# WMCB-V2.net
KiCad netlist of a schematic drawn in Altium Designer
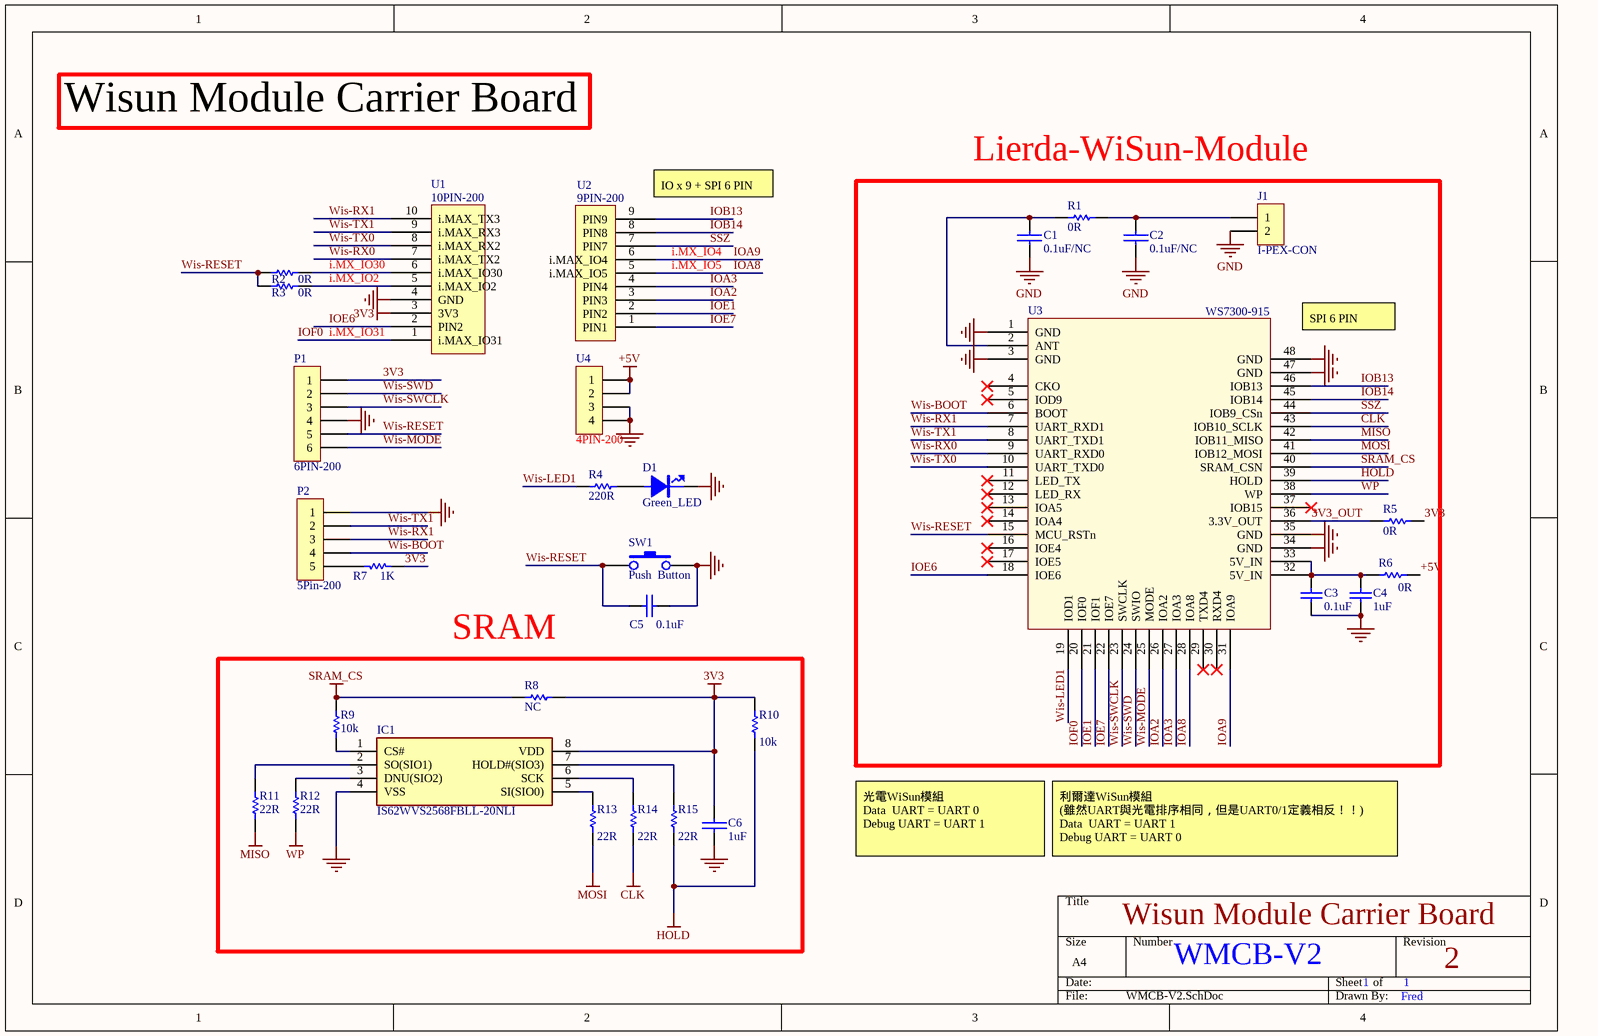
[diagram p0: WMCB-V2.SchDoc]

(export (version "E")
  (design (tool "Eeschema 10.0.6"))
  (components
    (comp (ref "C1")
      (value "0.1uF/NC")
      (footprint "0402C")
      (description "Capacitor")
      (libsource (lib "*") (part "CAP"))
    )
    (comp (ref "C2")
      (value "0.1uF/NC")
      (footprint "0402C")
      (description "Capacitor")
      (libsource (lib "*") (part "CAP"))
    )
    (comp (ref "C3")
      (value "0.1uF")
      (footprint "0603C")
      (description "Capacitor (Semiconductor SIM Model)")
      (fields (field (name "PUBLISHER") "Altium Limited"))
      (libsource (lib "*") (part "Cap Semi"))
    )
    (comp (ref "C4")
      (value "1uF")
      (footprint "0603C")
      (description "Capacitor (Semiconductor SIM Model)")
      (fields (field (name "Comment") "0.1uF") (field (name "PUBLISHER") "Altium Limited"))
      (libsource (lib "*") (part "Cap Semi"))
    )
    (comp (ref "C5")
      (value "0.1uF")
      (footprint "0402C")
      (description "Capacitor (Semiconductor SIM Model)")
      (fields (field (name "PUBLISHER") "Altium Limited"))
      (libsource (lib "*") (part "Cap Semi"))
    )
    (comp (ref "C6")
      (value "1uF")
      (footprint "0402C")
      (description "Capacitor")
      (libsource (lib "CAP") (part "CAP"))
    )
    (comp (ref "D1")
      (value "Green_LED")
      (footprint "LED0603--0.4mm")
      (fields
        (field (name "MANUFACTURER'S PART NUMBER") "CL-170G-CD-T")
        (field (name "PART NUMBER") "41100017000")
        (field (name "MANUFACTURER") "Citizen")
      )
      (libsource (lib "*") (part "LED"))
    )
    (comp (ref "IC1")
      (value "IS62WVS2568FBLL-20NLI")
      (footprint "SamacSys:SOIC127P600X175-8N")
      (description "Integrated Circuit")
      (fields (field (name "MOUSER2 PART NUMBER") "870-WVS2568FBLL20NLI"))
      (libsource (lib "*") (part "IS62WVS2568FBLL-20NLI"))
    )
    (comp (ref "J1")
      (value "I-PEX-CON")
      (footprint "I-PEX-CON")
      (description "Connector")
      (libsource (lib "*") (part "CON2"))
    )
    (comp (ref "P1")
      (value "6PIN-200")
      (footprint "6PIN-200")
      (description "Pin Header")
      (fields (field (name "PUBLISHER") "Altium Limited"))
      (libsource (lib "Miscellaneous Connectors") (part "6PIN-200"))
    )
    (comp (ref "P2") (value "5Pin-200") (footprint "5pin-200") (libsource (lib "PIN") (part "PIN5")))
    (comp (ref "R1")
      (value "0R")
      (footprint "0603")
      (description "Semiconductor Resistor")
      (fields (field (name "PUBLISHER") "Altium Limited"))
      (libsource (lib "*") (part "Res Semi"))
    )
    (comp (ref "R2")
      (value "0R")
      (footprint "0402")
      (description "Semiconductor Resistor")
      (fields (field (name "PUBLISHER") "Altium Limited"))
      (libsource (lib "*") (part "Res Semi"))
    )
    (comp (ref "R3")
      (value "0R")
      (footprint "0402")
      (description "Semiconductor Resistor")
      (fields (field (name "PUBLISHER") "Altium Limited"))
      (libsource (lib "*") (part "Res Semi"))
    )
    (comp (ref "R4")
      (value "220R")
      (footprint "0402")
      (description "Semiconductor Resistor")
      (fields (field (name "PUBLISHER") "Altium Limited"))
      (libsource (lib "*") (part "Res Semi"))
    )
    (comp (ref "R5")
      (value "0R")
      (footprint "0603")
      (description "Semiconductor Resistor")
      (fields (field (name "PUBLISHER") "Altium Limited"))
      (libsource (lib "*") (part "Res Semi"))
    )
    (comp (ref "R6")
      (value "0R")
      (footprint "0603")
      (description "Semiconductor Resistor")
      (fields (field (name "PUBLISHER") "Altium Limited"))
      (libsource (lib "*") (part "Res Semi"))
    )
    (comp (ref "R7")
      (value "1K")
      (footprint "0402")
      (description "Semiconductor Resistor")
      (fields (field (name "PUBLISHER") "Altium Limited"))
      (libsource (lib "*") (part "Res Semi"))
    )
    (comp (ref "R8")
      (value "NC")
      (footprint "0402")
      (description "Semiconductor Resistor")
      (fields (field (name "PUBLISHER") "Altium Limited"))
      (libsource (lib "*") (part "Res Semi"))
    )
    (comp (ref "R9")
      (value "10k")
      (footprint "0402")
      (description "Semiconductor Resistor")
      (fields (field (name "PUBLISHER") "Altium Limited"))
      (libsource (lib "*") (part "Res Semi"))
    )
    (comp (ref "R10")
      (value "10k")
      (footprint "0402")
      (description "Semiconductor Resistor")
      (fields (field (name "PUBLISHER") "Altium Limited"))
      (libsource (lib "*") (part "Res Semi"))
    )
    (comp (ref "R11")
      (value "22R")
      (footprint "0402")
      (description "Semiconductor Resistor")
      (fields (field (name "PUBLISHER") "Altium Limited"))
      (libsource (lib "*") (part "Res Semi"))
    )
    (comp (ref "R12")
      (value "22R")
      (footprint "0402")
      (description "Semiconductor Resistor")
      (fields (field (name "PUBLISHER") "Altium Limited"))
      (libsource (lib "*") (part "Res Semi"))
    )
    (comp (ref "R13")
      (value "22R")
      (footprint "0402")
      (description "Semiconductor Resistor")
      (fields (field (name "PUBLISHER") "Altium Limited"))
      (libsource (lib "*") (part "Res Semi"))
    )
    (comp (ref "R14")
      (value "22R")
      (footprint "0402")
      (description "Semiconductor Resistor")
      (fields (field (name "PUBLISHER") "Altium Limited"))
      (libsource (lib "*") (part "Res Semi"))
    )
    (comp (ref "R15")
      (value "22R")
      (footprint "0402")
      (description "Semiconductor Resistor")
      (fields (field (name "PUBLISHER") "Altium Limited"))
      (libsource (lib "*") (part "Res Semi"))
    )
    (comp (ref "SW1")
      (value "Push  Button")
      (footprint "Button_2pin-3*4*2MM")
      (description "Push Button")
      (libsource (lib "*") (part "SW1"))
    )
    (comp (ref "U1") (value "10PIN-200") (footprint "10PIN-200") (libsource (lib "*") (part "10PIN-200")))
    (comp (ref "U2") (value "9PIN-200") (footprint "9PIN-200") (libsource (lib "*") (part "9PIN-200")))
    (comp (ref "U3")
      (value "WS7300-915")
      (footprint "WiSun-Lierda")
      (libsource (lib "MODULE") (part "WS7300-915"))
    )
    (comp (ref "U4")
      (value "4PIN-200")
      (footprint "4PIN-200")
      (description "Connector")
      (libsource (lib "*") (part "CON4"))
    )
  )
  (nets
    (net (code "1") (name "+5V") (class "Default")
      (node (ref "R6") (pin "1") (pinfunction "1_1") (pintype "passive"))
      (node (ref "U4") (pin "1") (pinfunction "1_1") (pintype "passive"))
      (node (ref "U4") (pin "2") (pinfunction "2_2") (pintype "passive"))
    )
    (net (code "2") (name "/3V3_OUT") (class "Default")
      (node (ref "R5") (pin "2") (pinfunction "2_2") (pintype "passive"))
      (node (ref "U3") (pin "36") (pinfunction "3.3V_OUT_36") (pintype "passive"))
    )
    (net (code "3") (name "/IOA2") (class "Default")
      (node (ref "U2") (pin "3") (pinfunction "PIN3_3") (pintype "passive"))
      (node (ref "U3") (pin "26") (pinfunction "IOA2_26") (pintype "passive"))
    )
    (net (code "4") (name "/IOA3") (class "Default")
      (node (ref "U2") (pin "4") (pinfunction "PIN4_4") (pintype "passive"))
      (node (ref "U3") (pin "27") (pinfunction "IOA3_27") (pintype "passive"))
    )
    (net (code "5") (name "/IOA8") (class "Default")
      (node (ref "U2") (pin "5") (pinfunction "i.MAX_IO5_5") (pintype "passive"))
      (node (ref "U3") (pin "28") (pinfunction "IOA8_28") (pintype "passive"))
    )
    (net (code "6") (name "/IOA9") (class "Default")
      (node (ref "U2") (pin "6") (pinfunction "i.MAX_IO4_6") (pintype "passive"))
      (node (ref "U3") (pin "31") (pinfunction "IOA9_31") (pintype "passive"))
    )
    (net (code "7") (name "/IOB13") (class "Default")
      (node (ref "U2") (pin "9") (pinfunction "PIN9_9") (pintype "passive"))
      (node (ref "U3") (pin "46") (pinfunction "IOB13_46") (pintype "passive"))
    )
    (net (code "8") (name "/IOB14") (class "Default")
      (node (ref "U2") (pin "8") (pinfunction "PIN8_8") (pintype "passive"))
      (node (ref "U3") (pin "45") (pinfunction "IOB14_45") (pintype "passive"))
    )
    (net (code "9") (name "/IOE1") (class "Default")
      (node (ref "U2") (pin "2") (pinfunction "PIN2_2") (pintype "passive"))
      (node (ref "U3") (pin "21") (pinfunction "IOF1_21") (pintype "passive"))
    )
    (net (code "10") (name "/IOE6") (class "Default")
      (node (ref "U1") (pin "2") (pinfunction "PIN2_2") (pintype "passive"))
      (node (ref "U3") (pin "18") (pinfunction "IOE6_18") (pintype "passive"))
    )
    (net (code "11") (name "/IOE7") (class "Default")
      (node (ref "U2") (pin "1") (pinfunction "PIN1_1") (pintype "passive"))
      (node (ref "U3") (pin "22") (pinfunction "IOE7_22") (pintype "passive"))
    )
    (net (code "12") (name "/IOF0") (class "Default")
      (node (ref "U1") (pin "1") (pinfunction "i.MAX_IO31_1") (pintype "passive"))
      (node (ref "U3") (pin "20") (pinfunction "IOF0_20") (pintype "passive"))
    )
    (net (code "13") (name "/SSZ") (class "Default")
      (node (ref "U2") (pin "7") (pinfunction "PIN7_7") (pintype "passive"))
      (node (ref "U3") (pin "44") (pinfunction "IOB9_CSn_44") (pintype "passive"))
    )
    (net (code "14") (name "/Wis-BOOT") (class "Default")
      (node (ref "P2") (pin "4") (pinfunction "4_4") (pintype "passive"))
      (node (ref "U3") (pin "6") (pinfunction "BOOT_6") (pintype "passive"))
    )
    (net (code "15") (name "/Wis-LED1") (class "Default")
      (node (ref "R4") (pin "2") (pinfunction "2_2") (pintype "passive"))
      (node (ref "U3") (pin "19") (pinfunction "IOD1_19") (pintype "passive"))
    )
    (net (code "16") (name "/Wis-MODE") (class "Default")
      (node (ref "P1") (pin "6") (pinfunction "6_6") (pintype "passive"))
      (node (ref "U3") (pin "25") (pinfunction "MODE_25") (pintype "passive"))
    )
    (net (code "17") (name "/Wis-RESET") (class "Default")
      (node (ref "C5") (pin "1") (pinfunction "1_1") (pintype "passive"))
      (node (ref "P1") (pin "5") (pinfunction "5_5") (pintype "passive"))
      (node (ref "R2") (pin "2") (pinfunction "2_2") (pintype "passive"))
      (node (ref "R3") (pin "2") (pinfunction "2_2") (pintype "passive"))
      (node (ref "SW1") (pin "1") (pinfunction "1_1") (pintype "passive"))
      (node (ref "U3") (pin "15") (pinfunction "MCU_RSTn_15") (pintype "passive"))
    )
    (net (code "18") (name "/Wis-RX0") (class "Default")
      (node (ref "U1") (pin "7") (pinfunction "i.MAX_TX2_7") (pintype "passive"))
      (node (ref "U3") (pin "9") (pinfunction "UART_RXD0_9") (pintype "passive"))
    )
    (net (code "19") (name "/Wis-RX1") (class "Default")
      (node (ref "P2") (pin "3") (pinfunction "3_3") (pintype "passive"))
      (node (ref "U1") (pin "10") (pinfunction "i.MAX_TX3_10") (pintype "passive"))
      (node (ref "U3") (pin "7") (pinfunction "UART_RXD1_7") (pintype "passive"))
    )
    (net (code "20") (name "/Wis-SWCLK") (class "Default")
      (node (ref "P1") (pin "3") (pinfunction "3_3") (pintype "passive"))
      (node (ref "U3") (pin "23") (pinfunction "SWCLK_23") (pintype "passive"))
    )
    (net (code "21") (name "/Wis-SWD") (class "Default")
      (node (ref "P1") (pin "2") (pinfunction "2_2") (pintype "passive"))
      (node (ref "U3") (pin "24") (pinfunction "SWIO_24") (pintype "passive"))
    )
    (net (code "22") (name "/Wis-TX0") (class "Default")
      (node (ref "U1") (pin "8") (pinfunction "i.MAX_RX2_8") (pintype "passive"))
      (node (ref "U3") (pin "10") (pinfunction "UART_TXD0_10") (pintype "passive"))
    )
    (net (code "23") (name "/Wis-TX1") (class "Default")
      (node (ref "P2") (pin "2") (pinfunction "2_2") (pintype "passive"))
      (node (ref "U1") (pin "9") (pinfunction "i.MAX_RX3_9") (pintype "passive"))
      (node (ref "U3") (pin "8") (pinfunction "UART_TXD1_8") (pintype "passive"))
    )
    (net (code "24") (name "/i.MX_IO2") (class "Default")
      (node (ref "R3") (pin "1") (pinfunction "1_1") (pintype "passive"))
      (node (ref "U1") (pin "5") (pinfunction "i.MAX_IO2_5") (pintype "passive"))
    )
    (net (code "25") (name "/i.MX_IO30") (class "Default")
      (node (ref "R2") (pin "1") (pinfunction "1_1") (pintype "passive"))
      (node (ref "U1") (pin "6") (pinfunction "i.MAX_IO30_6") (pintype "passive"))
    )
    (net (code "26") (name "3V3") (class "Default")
      (node (ref "C6") (pin "2") (pinfunction "2_2") (pintype "passive"))
      (node (ref "IC1") (pin "8") (pinfunction "VDD_8") (pintype "passive"))
      (node (ref "P1") (pin "1") (pinfunction "1_1") (pintype "passive"))
      (node (ref "R10") (pin "2") (pinfunction "2_2") (pintype "passive"))
      (node (ref "R5") (pin "1") (pinfunction "1_1") (pintype "passive"))
      (node (ref "R7") (pin "1") (pinfunction "1_1") (pintype "passive"))
      (node (ref "R8") (pin "1") (pinfunction "1_1") (pintype "passive"))
      (node (ref "U1") (pin "3") (pinfunction "3V3_3") (pintype "passive"))
    )
    (net (code "27") (name "CLK") (class "Default")
      (node (ref "R14") (pin "1") (pinfunction "1_1") (pintype "passive"))
      (node (ref "U3") (pin "43") (pinfunction "IOB10_SCLK_43") (pintype "passive"))
    )
    (net (code "28") (name "GND") (class "Default")
      (node (ref "C1") (pin "1") (pinfunction "1_1") (pintype "passive"))
      (node (ref "C2") (pin "1") (pinfunction "1_1") (pintype "passive"))
      (node (ref "C3") (pin "1") (pinfunction "1_1") (pintype "passive"))
      (node (ref "C4") (pin "2") (pinfunction "2_2") (pintype "passive"))
      (node (ref "C5") (pin "2") (pinfunction "2_2") (pintype "passive"))
      (node (ref "C6") (pin "1") (pinfunction "1_1") (pintype "passive"))
      (node (ref "D1") (pin "2") (pinfunction "2_2") (pintype "passive"))
      (node (ref "IC1") (pin "4") (pinfunction "VSS_4") (pintype "passive"))
      (node (ref "J1") (pin "2") (pinfunction "2_2") (pintype "passive"))
      (node (ref "P1") (pin "4") (pinfunction "4_4") (pintype "passive"))
      (node (ref "P2") (pin "1") (pinfunction "1_1") (pintype "passive"))
      (node (ref "SW1") (pin "2") (pinfunction "2_2") (pintype "passive"))
      (node (ref "U1") (pin "4") (pinfunction "GND_4") (pintype "passive"))
      (node (ref "U3") (pin "1") (pinfunction "GND_1") (pintype "passive"))
      (node (ref "U3") (pin "3") (pinfunction "GND_3") (pintype "passive"))
      (node (ref "U3") (pin "34") (pinfunction "GND_34") (pintype "passive"))
      (node (ref "U3") (pin "35") (pinfunction "GND_35") (pintype "passive"))
      (node (ref "U3") (pin "47") (pinfunction "GND_47") (pintype "passive"))
      (node (ref "U3") (pin "48") (pinfunction "GND_48") (pintype "passive"))
      (node (ref "U4") (pin "3") (pinfunction "3_3") (pintype "passive"))
      (node (ref "U4") (pin "4") (pinfunction "4_4") (pintype "passive"))
    )
    (net (code "29") (name "HOLD") (class "Default")
      (node (ref "R10") (pin "1") (pinfunction "1_1") (pintype "passive"))
      (node (ref "R15") (pin "1") (pinfunction "1_1") (pintype "passive"))
      (node (ref "U3") (pin "39") (pinfunction "HOLD_39") (pintype "passive"))
    )
    (net (code "30") (name "MISO") (class "Default")
      (node (ref "R11") (pin "2") (pinfunction "2_2") (pintype "passive"))
      (node (ref "U3") (pin "42") (pinfunction "IOB11_MISO_42") (pintype "passive"))
    )
    (net (code "31") (name "MOSI") (class "Default")
      (node (ref "R13") (pin "1") (pinfunction "1_1") (pintype "passive"))
      (node (ref "U3") (pin "41") (pinfunction "IOB12_MOSI_41") (pintype "passive"))
    )
    (net (code "32") (name "Net-(C2-Pad2)") (class "Default")
      (node (ref "C2") (pin "2") (pinfunction "2_2") (pintype "passive"))
      (node (ref "J1") (pin "1") (pinfunction "1_1") (pintype "passive"))
      (node (ref "R1") (pin "2") (pinfunction "2_2") (pintype "passive"))
    )
    (net (code "33") (name "Net-(C3-Pad2)") (class "Default")
      (node (ref "C3") (pin "2") (pinfunction "2_2") (pintype "passive"))
      (node (ref "C4") (pin "1") (pinfunction "1_1") (pintype "passive"))
      (node (ref "R6") (pin "2") (pinfunction "2_2") (pintype "passive"))
      (node (ref "U3") (pin "32") (pinfunction "5V_IN_32") (pintype "passive"))
      (node (ref "U3") (pin "33") (pinfunction "5V_IN_33") (pintype "passive"))
    )
    (net (code "34") (name "Net-(D1-Pad1)") (class "Default")
      (node (ref "D1") (pin "1") (pinfunction "1_1") (pintype "passive"))
      (node (ref "R4") (pin "1") (pinfunction "1_1") (pintype "passive"))
    )
    (net (code "35") (name "Net-(IC1-CS#)") (class "Default")
      (node (ref "IC1") (pin "1") (pinfunction "CS#_1") (pintype "passive"))
      (node (ref "R9") (pin "2") (pinfunction "2_2") (pintype "passive"))
    )
    (net (code "36") (name "Net-(IC1-DNU(SIO2))") (class "Default")
      (node (ref "IC1") (pin "3") (pinfunction "DNU(SIO2)_3") (pintype "passive"))
      (node (ref "R12") (pin "2") (pinfunction "2_2") (pintype "passive"))
    )
    (net (code "37") (name "Net-(IC1-HOLD#(SIO3))") (class "Default")
      (node (ref "IC1") (pin "7") (pinfunction "HOLD#(SIO3)_7") (pintype "passive"))
      (node (ref "R15") (pin "2") (pinfunction "2_2") (pintype "passive"))
    )
    (net (code "38") (name "Net-(IC1-SCK)") (class "Default")
      (node (ref "IC1") (pin "6") (pinfunction "SCK_6") (pintype "passive"))
      (node (ref "R14") (pin "2") (pinfunction "2_2") (pintype "passive"))
    )
    (net (code "39") (name "Net-(IC1-SI(SIO0))") (class "Default")
      (node (ref "IC1") (pin "5") (pinfunction "SI(SIO0)_5") (pintype "passive"))
      (node (ref "R13") (pin "2") (pinfunction "2_2") (pintype "passive"))
    )
    (net (code "40") (name "Net-(IC1-SO(SIO1))") (class "Default")
      (node (ref "IC1") (pin "2") (pinfunction "SO(SIO1)_2") (pintype "passive"))
      (node (ref "R11") (pin "1") (pinfunction "1_1") (pintype "passive"))
    )
    (net (code "41") (name "Net-(P2-Pad5)") (class "Default")
      (node (ref "P2") (pin "5") (pinfunction "5_5") (pintype "passive"))
      (node (ref "R7") (pin "2") (pinfunction "2_2") (pintype "passive"))
    )
    (net (code "42") (name "Net-(U3-ANT)") (class "Default")
      (node (ref "C1") (pin "2") (pinfunction "2_2") (pintype "passive"))
      (node (ref "R1") (pin "1") (pinfunction "1_1") (pintype "passive"))
      (node (ref "U3") (pin "2") (pinfunction "ANT_2") (pintype "passive"))
    )
    (net (code "43") (name "SRAM_CS") (class "Default")
      (node (ref "R8") (pin "2") (pinfunction "2_2") (pintype "passive"))
      (node (ref "R9") (pin "1") (pinfunction "1_1") (pintype "passive"))
      (node (ref "U3") (pin "40") (pinfunction "SRAM_CSN_40") (pintype "passive"))
    )
    (net (code "44") (name "WP") (class "Default")
      (node (ref "R12") (pin "1") (pinfunction "1_1") (pintype "passive"))
      (node (ref "U3") (pin "38") (pinfunction "WP_38") (pintype "passive"))
    )
    (net (code "45") (name "unconnected-(U3-CKO-Pad4)") (class "Default")
      (node (ref "U3") (pin "4") (pinfunction "CKO_4") (pintype "passive+no_connect"))
    )
    (net (code "46") (name "unconnected-(U3-IOA4-Pad14)") (class "Default")
      (node (ref "U3") (pin "14") (pinfunction "IOA4_14") (pintype "passive+no_connect"))
    )
    (net (code "47") (name "unconnected-(U3-IOA5-Pad13)") (class "Default")
      (node (ref "U3") (pin "13") (pinfunction "IOA5_13") (pintype "passive+no_connect"))
    )
    (net (code "48") (name "unconnected-(U3-IOB15-Pad37)") (class "Default")
      (node (ref "U3") (pin "37") (pinfunction "IOB15_37") (pintype "passive+no_connect"))
    )
    (net (code "49") (name "unconnected-(U3-IOD9-Pad5)") (class "Default")
      (node (ref "U3") (pin "5") (pinfunction "IOD9_5") (pintype "passive+no_connect"))
    )
    (net (code "50") (name "unconnected-(U3-IOE4-Pad16)") (class "Default")
      (node (ref "U3") (pin "16") (pinfunction "IOE4_16") (pintype "passive+no_connect"))
    )
    (net (code "51") (name "unconnected-(U3-IOE5-Pad17)") (class "Default")
      (node (ref "U3") (pin "17") (pinfunction "IOE5_17") (pintype "passive+no_connect"))
    )
    (net (code "52") (name "unconnected-(U3-LED_RX-Pad12)") (class "Default")
      (node (ref "U3") (pin "12") (pinfunction "LED_RX_12") (pintype "passive+no_connect"))
    )
    (net (code "53") (name "unconnected-(U3-LED_TX-Pad11)") (class "Default")
      (node (ref "U3") (pin "11") (pinfunction "LED_TX_11") (pintype "passive+no_connect"))
    )
    (net (code "54") (name "unconnected-(U3-RXD4-Pad30)") (class "Default")
      (node (ref "U3") (pin "30") (pinfunction "RXD4_30") (pintype "passive+no_connect"))
    )
    (net (code "55") (name "unconnected-(U3-TXD4-Pad29)") (class "Default")
      (node (ref "U3") (pin "29") (pinfunction "TXD4_29") (pintype "passive+no_connect"))
    )
  )
)
